# led_dimmer.net
KiCad netlist of a schematic drawn in EAGLE
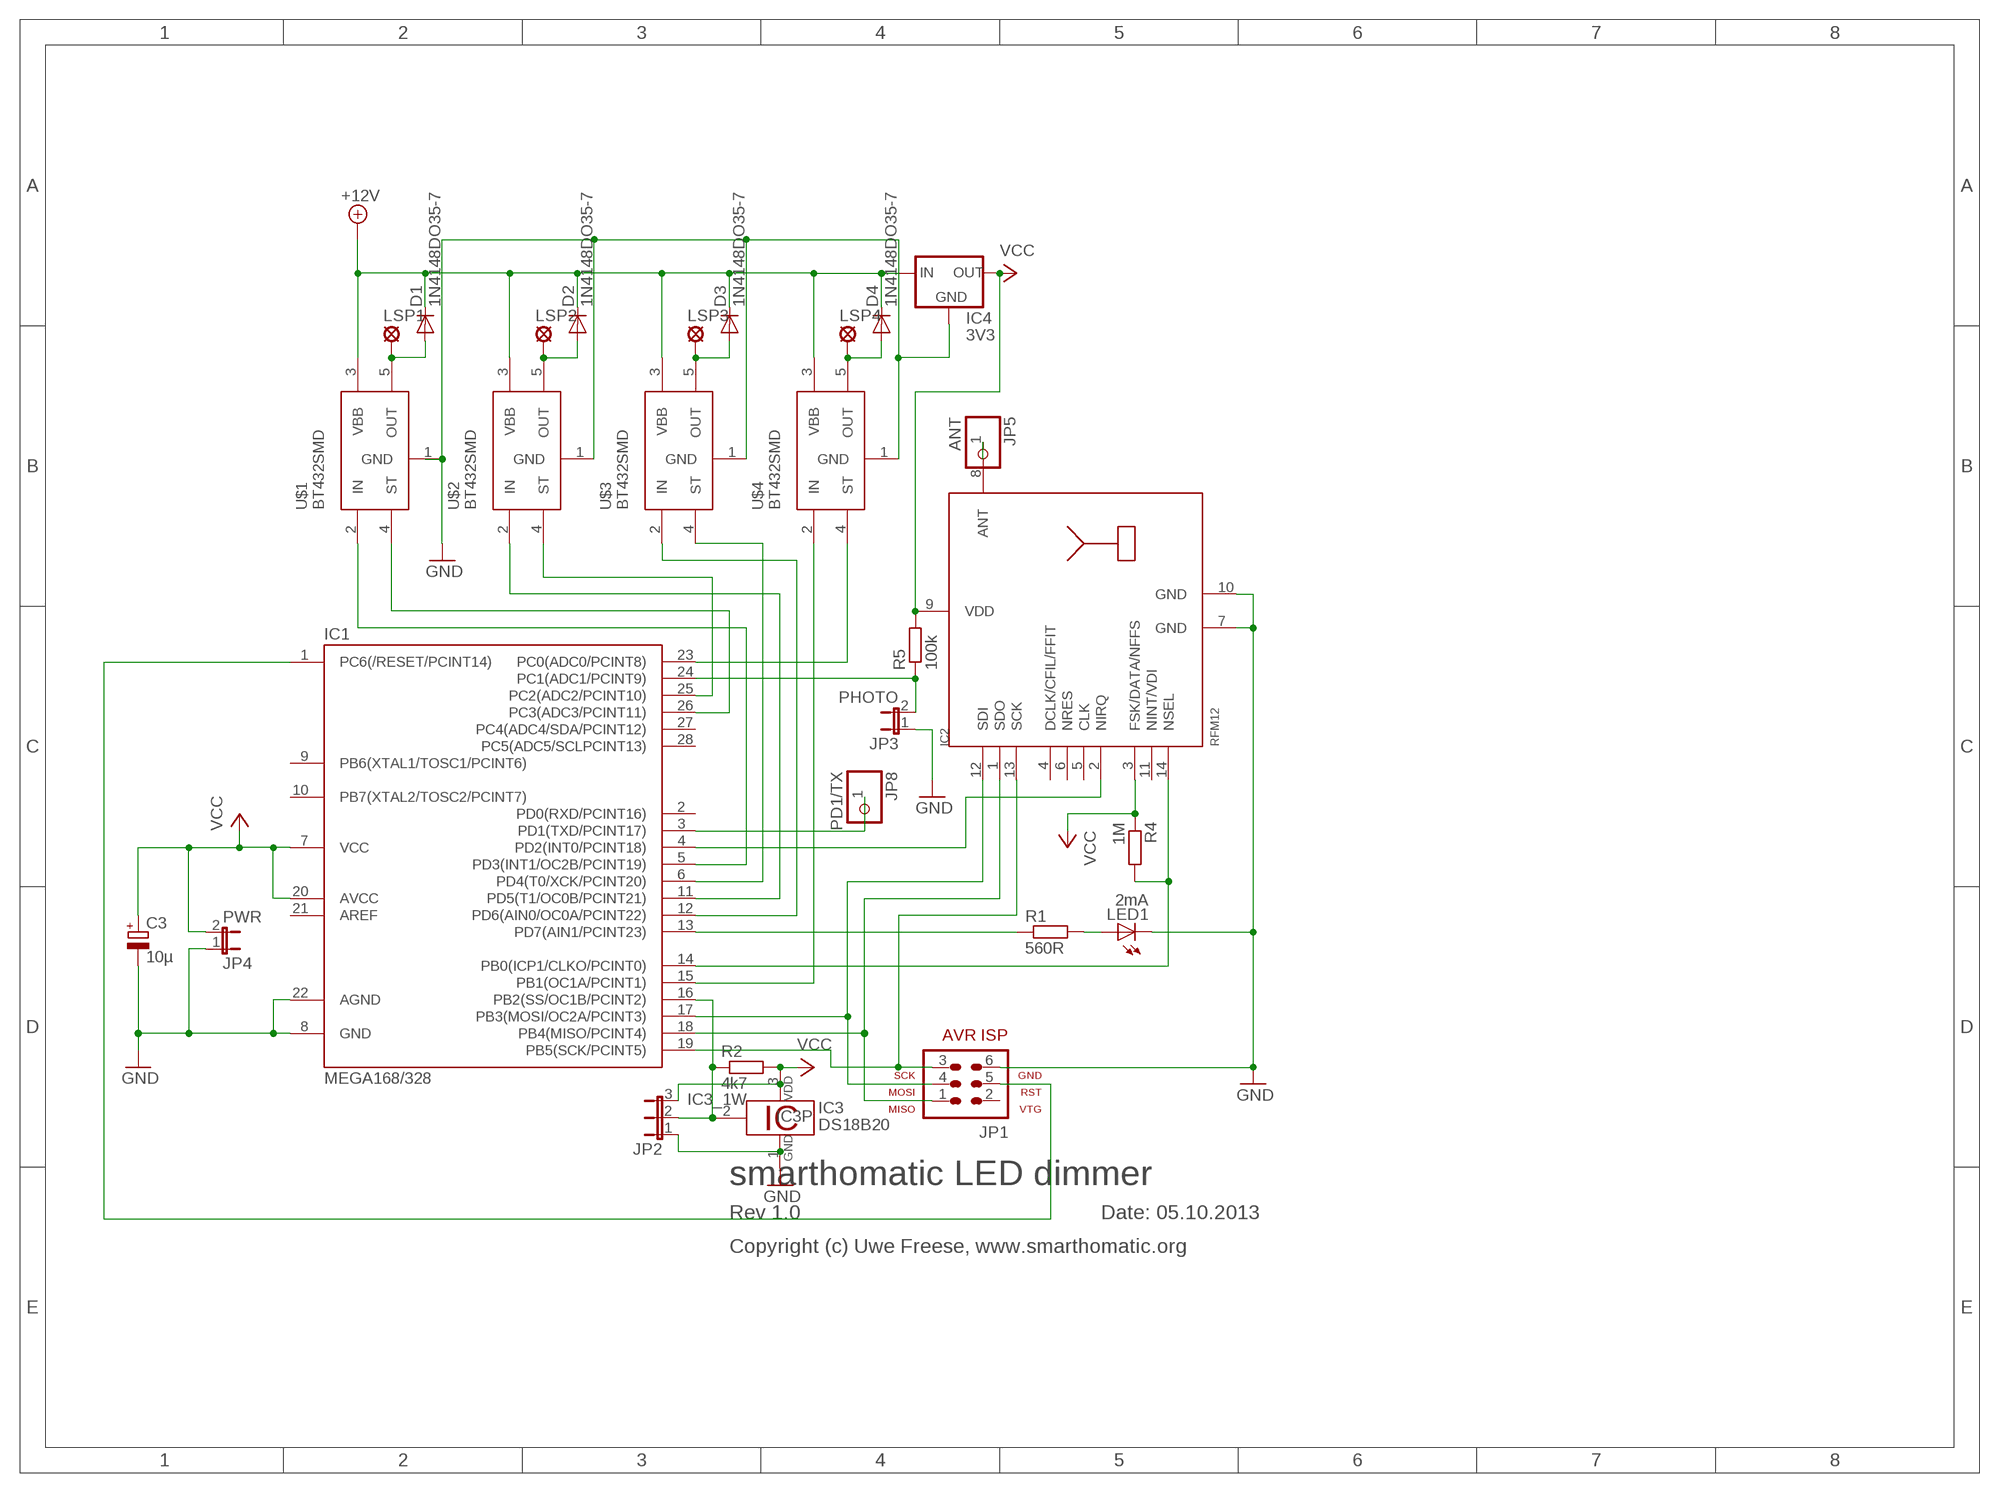
[diagram p0: schematic, sheet 1]

(export (version "E")
  (design (tool "Eeschema 10.0.6"))
  (components
    (comp (ref "C3")
      (value "10µ")
      (footprint "eagle-import:E2,5-6")
      (libsource (lib "eagle-import") (part "CPOL-EUE2.5-6"))
    )
    (comp (ref "D1")
      (value "1N4148DO35-7")
      (footprint "eagle-import:DO35-7")
      (libsource (lib "eagle-import") (part "1N4148DO35-7"))
    )
    (comp (ref "D2")
      (value "1N4148DO35-7")
      (footprint "eagle-import:DO35-7")
      (libsource (lib "eagle-import") (part "1N4148DO35-7"))
    )
    (comp (ref "D3")
      (value "1N4148DO35-7")
      (footprint "eagle-import:DO35-7")
      (libsource (lib "eagle-import") (part "1N4148DO35-7"))
    )
    (comp (ref "D4")
      (value "1N4148DO35-7")
      (footprint "eagle-import:DO35-7")
      (libsource (lib "eagle-import") (part "1N4148DO35-7"))
    )
    (comp (ref "IC1")
      (value "MEGA168/328")
      (footprint "eagle-import:DIL28-3")
      (libsource (lib "eagle-import") (part "MEGA48/88/168-PU"))
    )
    (comp (ref "IC2")
      (value "RFM12")
      (footprint "eagle-import:RFM")
      (libsource (lib "eagle-import") (part "RFM12"))
    )
    (comp (ref "IC3")
      (value "DS18B20")
      (footprint "eagle-import:TO92-")
      (libsource (lib "eagle-import") (part "DS18B20"))
    )
    (comp (ref "IC4")
      (value "3V3")
      (footprint "eagle-import:78LXX")
      (libsource (lib "eagle-import") (part "78LXX"))
    )
    (comp (ref "JP1")
      (value "AVR-ISP-6")
      (footprint "eagle-import:AVR-ISP-6")
      (libsource (lib "eagle-import") (part "AVR-ISP-6"))
    )
    (comp (ref "JP2")
      (value "JP2E")
      (footprint "eagle-import:JP2")
      (libsource (lib "eagle-import") (part "JP2E"))
    )
    (comp (ref "JP3")
      (value "PHOTO")
      (footprint "eagle-import:JP1")
      (libsource (lib "eagle-import") (part "JP1E"))
    )
    (comp (ref "JP4")
      (value "PWR")
      (footprint "eagle-import:JP1")
      (libsource (lib "eagle-import") (part "JP1E"))
    )
    (comp (ref "JP5")
      (value "ANT")
      (footprint "eagle-import:1X01")
      (libsource (lib "eagle-import") (part "PINHD-1X1"))
    )
    (comp (ref "JP8")
      (value "PD1/TX")
      (footprint "eagle-import:1X01")
      (libsource (lib "eagle-import") (part "PINHD-1X1"))
    )
    (comp (ref "LED1")
      (value "2mA")
      (footprint "eagle-import:LED3MM")
      (libsource (lib "eagle-import") (part "LED3MM"))
    )
    (comp (ref "LSP1")
      (value "MCS10B")
      (footprint "eagle-import:MCS10B")
      (libsource (lib "eagle-import") (part "MCS10B"))
    )
    (comp (ref "LSP2")
      (value "MCS10B")
      (footprint "eagle-import:MCS10B")
      (libsource (lib "eagle-import") (part "MCS10B"))
    )
    (comp (ref "LSP3")
      (value "MCS10B")
      (footprint "eagle-import:MCS10B")
      (libsource (lib "eagle-import") (part "MCS10B"))
    )
    (comp (ref "LSP4")
      (value "MCS10B")
      (footprint "eagle-import:MCS10B")
      (libsource (lib "eagle-import") (part "MCS10B"))
    )
    (comp (ref "R1")
      (value "560R")
      (footprint "eagle-import:0207_7")
      (libsource (lib "eagle-import") (part "R-EU_0207/7"))
    )
    (comp (ref "R2")
      (value "4k7")
      (footprint "eagle-import:0207_7")
      (libsource (lib "eagle-import") (part "resistor_R-EU_0207/7"))
    )
    (comp (ref "R4")
      (value "1M")
      (footprint "eagle-import:0207_7")
      (libsource (lib "eagle-import") (part "R-EU_0207/7"))
    )
    (comp (ref "R5")
      (value "100k")
      (footprint "eagle-import:0207_7")
      (libsource (lib "eagle-import") (part "R-EU_0207/7"))
    )
    (comp (ref "U$1")
      (value "BT432SMD")
      (footprint "eagle-import:TO220-58")
      (libsource (lib "eagle-import") (part "BT432SMD"))
    )
    (comp (ref "U$2")
      (value "BT432SMD")
      (footprint "eagle-import:TO220-58")
      (libsource (lib "eagle-import") (part "BT432SMD"))
    )
    (comp (ref "U$3")
      (value "BT432SMD")
      (footprint "eagle-import:TO220-58")
      (libsource (lib "eagle-import") (part "BT432SMD"))
    )
    (comp (ref "U$4")
      (value "BT432SMD")
      (footprint "eagle-import:TO220-58")
      (libsource (lib "eagle-import") (part "BT432SMD"))
    )
  )
  (nets
    (net (code "1") (name "+12V") (class "Default")
      (node (ref "D1") (pin "C") (pinfunction "C_C") (pintype "passive"))
      (node (ref "D2") (pin "C") (pinfunction "C_C") (pintype "passive"))
      (node (ref "D3") (pin "C") (pinfunction "C_C") (pintype "passive"))
      (node (ref "D4") (pin "C") (pinfunction "C_C") (pintype "passive"))
      (node (ref "IC4") (pin "IN") (pinfunction "IN_IN") (pintype "input"))
      (node (ref "U$1") (pin "3") (pinfunction "VBB_3") (pintype "bidirectional"))
      (node (ref "U$2") (pin "3") (pinfunction "VBB_3") (pintype "bidirectional"))
      (node (ref "U$3") (pin "3") (pinfunction "VBB_3") (pintype "bidirectional"))
      (node (ref "U$4") (pin "3") (pinfunction "VBB_3") (pintype "bidirectional"))
    )
    (net (code "2") (name "GND") (class "Default")
      (node (ref "C3") (pin "-") (pinfunction "-_-") (pintype "passive"))
      (node (ref "IC1") (pin "22") (pinfunction "AGND_22") (pintype "power_in"))
      (node (ref "IC1") (pin "8") (pinfunction "GND_8") (pintype "power_in"))
      (node (ref "IC2") (pin "10") (pinfunction "GND_10") (pintype "power_in"))
      (node (ref "IC2") (pin "7") (pinfunction "GND_7") (pintype "power_in"))
      (node (ref "IC3") (pin "1") (pinfunction "GND_1") (pintype "power_in"))
      (node (ref "IC4") (pin "GND") (pinfunction "GND_GND") (pintype "input"))
      (node (ref "JP1") (pin "6") (pinfunction "6_6") (pintype "passive"))
      (node (ref "JP2") (pin "1") (pinfunction "1_1") (pintype "passive"))
      (node (ref "JP3") (pin "1") (pinfunction "1_1") (pintype "passive"))
      (node (ref "JP4") (pin "1") (pinfunction "1_1") (pintype "passive"))
      (node (ref "LED1") (pin "K") (pinfunction "C_K") (pintype "passive"))
      (node (ref "U$1") (pin "1") (pinfunction "GND_1") (pintype "bidirectional"))
      (node (ref "U$2") (pin "1") (pinfunction "GND_1") (pintype "bidirectional"))
      (node (ref "U$3") (pin "1") (pinfunction "GND_1") (pintype "bidirectional"))
      (node (ref "U$4") (pin "1") (pinfunction "GND_1") (pintype "bidirectional"))
    )
    (net (code "3") (name "Net-(IC1-PB0(ICP1{slash}CLKO{slash}PCINT0))") (class "Default")
      (node (ref "IC1") (pin "14") (pinfunction "PB0(ICP1/CLKO/PCINT0)_14") (pintype "bidirectional"))
      (node (ref "IC2") (pin "14") (pinfunction "NSEL_14") (pintype "bidirectional"))
      (node (ref "R4") (pin "2") (pinfunction "2_2") (pintype "passive"))
    )
    (net (code "4") (name "Net-(IC1-PB1(OC1A{slash}PCINT1))") (class "Default")
      (node (ref "IC1") (pin "15") (pinfunction "PB1(OC1A/PCINT1)_15") (pintype "bidirectional"))
      (node (ref "U$4") (pin "2") (pinfunction "IN_2") (pintype "bidirectional"))
    )
    (net (code "5") (name "Net-(IC1-PB2(SS{slash}OC1B{slash}PCINT2))") (class "Default")
      (node (ref "IC1") (pin "16") (pinfunction "PB2(SS/OC1B/PCINT2)_16") (pintype "bidirectional"))
      (node (ref "IC3") (pin "2") (pinfunction "1W_2") (pintype "power_in"))
      (node (ref "JP2") (pin "2") (pinfunction "2_2") (pintype "passive"))
      (node (ref "R2") (pin "1") (pinfunction "1_1") (pintype "passive"))
    )
    (net (code "6") (name "Net-(IC1-PB3(MOSI{slash}OC2A{slash}PCINT3))") (class "Default")
      (node (ref "IC1") (pin "17") (pinfunction "PB3(MOSI/OC2A/PCINT3)_17") (pintype "bidirectional"))
      (node (ref "IC2") (pin "12") (pinfunction "SDI_12") (pintype "bidirectional"))
      (node (ref "JP1") (pin "4") (pinfunction "4_4") (pintype "passive"))
    )
    (net (code "7") (name "Net-(IC1-PB4(MISO{slash}PCINT4))") (class "Default")
      (node (ref "IC1") (pin "18") (pinfunction "PB4(MISO/PCINT4)_18") (pintype "bidirectional"))
      (node (ref "IC2") (pin "1") (pinfunction "SDO_1") (pintype "bidirectional"))
      (node (ref "JP1") (pin "1") (pinfunction "1_1") (pintype "passive"))
    )
    (net (code "8") (name "Net-(IC1-PB5(SCK{slash}PCINT5))") (class "Default")
      (node (ref "IC1") (pin "19") (pinfunction "PB5(SCK/PCINT5)_19") (pintype "bidirectional"))
      (node (ref "IC2") (pin "13") (pinfunction "SCK_13") (pintype "bidirectional"))
      (node (ref "JP1") (pin "3") (pinfunction "3_3") (pintype "passive"))
    )
    (net (code "9") (name "Net-(IC1-PC0(ADC0{slash}PCINT8))") (class "Default")
      (node (ref "IC1") (pin "23") (pinfunction "PC0(ADC0/PCINT8)_23") (pintype "bidirectional"))
      (node (ref "U$4") (pin "4") (pinfunction "ST_4") (pintype "bidirectional"))
    )
    (net (code "10") (name "Net-(IC1-PC1(ADC1{slash}PCINT9))") (class "Default")
      (node (ref "IC1") (pin "24") (pinfunction "PC1(ADC1/PCINT9)_24") (pintype "bidirectional"))
      (node (ref "JP3") (pin "2") (pinfunction "2_2") (pintype "passive"))
      (node (ref "R5") (pin "1") (pinfunction "1_1") (pintype "passive"))
    )
    (net (code "11") (name "Net-(IC1-PC2(ADC2{slash}PCINT10))") (class "Default")
      (node (ref "IC1") (pin "25") (pinfunction "PC2(ADC2/PCINT10)_25") (pintype "bidirectional"))
      (node (ref "U$2") (pin "4") (pinfunction "ST_4") (pintype "bidirectional"))
    )
    (net (code "12") (name "Net-(IC1-PC3(ADC3{slash}PCINT11))") (class "Default")
      (node (ref "IC1") (pin "26") (pinfunction "PC3(ADC3/PCINT11)_26") (pintype "bidirectional"))
      (node (ref "U$1") (pin "4") (pinfunction "ST_4") (pintype "bidirectional"))
    )
    (net (code "13") (name "Net-(IC1-PC6({slash}RESET{slash}PCINT14))") (class "Default")
      (node (ref "IC1") (pin "1") (pinfunction "PC6(/RESET/PCINT14)_1") (pintype "bidirectional"))
      (node (ref "JP1") (pin "5") (pinfunction "5_5") (pintype "passive"))
    )
    (net (code "14") (name "Net-(IC1-PD1(TXD{slash}PCINT17))") (class "Default")
      (node (ref "IC1") (pin "3") (pinfunction "PD1(TXD/PCINT17)_3") (pintype "bidirectional"))
      (node (ref "JP8") (pin "1") (pinfunction "1_1") (pintype "passive"))
    )
    (net (code "15") (name "Net-(IC1-PD2(INT0{slash}PCINT18))") (class "Default")
      (node (ref "IC1") (pin "4") (pinfunction "PD2(INT0/PCINT18)_4") (pintype "bidirectional"))
      (node (ref "IC2") (pin "2") (pinfunction "NIRQ_2") (pintype "bidirectional"))
    )
    (net (code "16") (name "Net-(IC1-PD3(INT1{slash}OC2B{slash}PCINT19))") (class "Default")
      (node (ref "IC1") (pin "5") (pinfunction "PD3(INT1/OC2B/PCINT19)_5") (pintype "bidirectional"))
      (node (ref "U$1") (pin "2") (pinfunction "IN_2") (pintype "bidirectional"))
    )
    (net (code "17") (name "Net-(IC1-PD4(T0{slash}XCK{slash}PCINT20))") (class "Default")
      (node (ref "IC1") (pin "6") (pinfunction "PD4(T0/XCK/PCINT20)_6") (pintype "bidirectional"))
      (node (ref "U$3") (pin "4") (pinfunction "ST_4") (pintype "bidirectional"))
    )
    (net (code "18") (name "Net-(IC1-PD5(T1{slash}OC0B{slash}PCINT21))") (class "Default")
      (node (ref "IC1") (pin "11") (pinfunction "PD5(T1/OC0B/PCINT21)_11") (pintype "bidirectional"))
      (node (ref "U$2") (pin "2") (pinfunction "IN_2") (pintype "bidirectional"))
    )
    (net (code "19") (name "Net-(IC1-PD6(AIN0{slash}OC0A{slash}PCINT22))") (class "Default")
      (node (ref "IC1") (pin "12") (pinfunction "PD6(AIN0/OC0A/PCINT22)_12") (pintype "bidirectional"))
      (node (ref "U$3") (pin "2") (pinfunction "IN_2") (pintype "bidirectional"))
    )
    (net (code "20") (name "Net-(IC1-PD7(AIN1{slash}PCINT23))") (class "Default")
      (node (ref "IC1") (pin "13") (pinfunction "PD7(AIN1/PCINT23)_13") (pintype "bidirectional"))
      (node (ref "R1") (pin "1") (pinfunction "1_1") (pintype "passive"))
    )
    (net (code "21") (name "Net-(IC2-ANT)") (class "Default")
      (node (ref "IC2") (pin "8") (pinfunction "ANT_8") (pintype "output"))
      (node (ref "JP5") (pin "1") (pinfunction "1_1") (pintype "passive"))
    )
    (net (code "22") (name "Net-(LED1-PadA)") (class "Default")
      (node (ref "LED1") (pin "A") (pinfunction "A_A") (pintype "passive"))
      (node (ref "R1") (pin "2") (pinfunction "2_2") (pintype "passive"))
    )
    (net (code "23") (name "Net-(U$1-OUT)") (class "Default")
      (node (ref "D1") (pin "A") (pinfunction "A_A") (pintype "passive"))
      (node (ref "LSP1") (pin "MP") (pinfunction "MP_MP") (pintype "passive"))
      (node (ref "U$1") (pin "5") (pinfunction "OUT_5") (pintype "bidirectional"))
    )
    (net (code "24") (name "Net-(U$2-OUT)") (class "Default")
      (node (ref "D2") (pin "A") (pinfunction "A_A") (pintype "passive"))
      (node (ref "LSP2") (pin "MP") (pinfunction "MP_MP") (pintype "passive"))
      (node (ref "U$2") (pin "5") (pinfunction "OUT_5") (pintype "bidirectional"))
    )
    (net (code "25") (name "Net-(U$3-OUT)") (class "Default")
      (node (ref "D3") (pin "A") (pinfunction "A_A") (pintype "passive"))
      (node (ref "LSP3") (pin "MP") (pinfunction "MP_MP") (pintype "passive"))
      (node (ref "U$3") (pin "5") (pinfunction "OUT_5") (pintype "bidirectional"))
    )
    (net (code "26") (name "Net-(U$4-OUT)") (class "Default")
      (node (ref "D4") (pin "A") (pinfunction "A_A") (pintype "passive"))
      (node (ref "LSP4") (pin "MP") (pinfunction "MP_MP") (pintype "passive"))
      (node (ref "U$4") (pin "5") (pinfunction "OUT_5") (pintype "bidirectional"))
    )
    (net (code "27") (name "VCC") (class "Default")
      (node (ref "C3") (pin "+") (pinfunction "+_+") (pintype "passive"))
      (node (ref "IC1") (pin "20") (pinfunction "AVCC_20") (pintype "passive"))
      (node (ref "IC1") (pin "7") (pinfunction "VCC_7") (pintype "power_in"))
      (node (ref "IC2") (pin "3") (pinfunction "FSK/DATA/NFFS_3") (pintype "bidirectional"))
      (node (ref "IC2") (pin "9") (pinfunction "VDD_9") (pintype "power_in"))
      (node (ref "IC3") (pin "3") (pinfunction "VDD_3") (pintype "power_in"))
      (node (ref "IC4") (pin "OUT") (pinfunction "OUT_OUT") (pintype "passive"))
      (node (ref "JP2") (pin "3") (pinfunction "3_3") (pintype "passive"))
      (node (ref "JP4") (pin "2") (pinfunction "2_2") (pintype "passive"))
      (node (ref "R2") (pin "2") (pinfunction "2_2") (pintype "passive"))
      (node (ref "R4") (pin "1") (pinfunction "1_1") (pintype "passive"))
      (node (ref "R5") (pin "2") (pinfunction "2_2") (pintype "passive"))
    )
    (net (code "28") (name "unconnected-(IC1-AREF-Pad21)") (class "Default")
      (node (ref "IC1") (pin "21") (pinfunction "AREF_21") (pintype "passive"))
    )
    (net (code "29") (name "unconnected-(IC1-PB6(XTAL1{slash}TOSC1{slash}PCINT6)-Pad9)") (class "Default")
      (node (ref "IC1") (pin "9") (pinfunction "PB6(XTAL1/TOSC1/PCINT6)_9") (pintype "bidirectional"))
    )
    (net (code "30") (name "unconnected-(IC1-PB7(XTAL2{slash}TOSC2{slash}PCINT7)-Pad10)") (class "Default")
      (node (ref "IC1") (pin "10") (pinfunction "PB7(XTAL2/TOSC2/PCINT7)_10") (pintype "bidirectional"))
    )
    (net (code "31") (name "unconnected-(IC1-PC4(ADC4{slash}SDA{slash}PCINT12)-Pad27)") (class "Default")
      (node (ref "IC1") (pin "27") (pinfunction "PC4(ADC4/SDA/PCINT12)_27") (pintype "bidirectional"))
    )
    (net (code "32") (name "unconnected-(IC1-PC5(ADC5{slash}SCLPCINT13)-Pad28)") (class "Default")
      (node (ref "IC1") (pin "28") (pinfunction "PC5(ADC5/SCLPCINT13)_28") (pintype "bidirectional"))
    )
    (net (code "33") (name "unconnected-(IC1-PD0(RXD{slash}PCINT16)-Pad2)") (class "Default")
      (node (ref "IC1") (pin "2") (pinfunction "PD0(RXD/PCINT16)_2") (pintype "bidirectional"))
    )
    (net (code "34") (name "unconnected-(IC2-CLK-Pad5)") (class "Default")
      (node (ref "IC2") (pin "5") (pinfunction "CLK_5") (pintype "bidirectional"))
    )
    (net (code "35") (name "unconnected-(IC2-DCLK{slash}CFIL{slash}FFIT-Pad4)") (class "Default")
      (node (ref "IC2") (pin "4") (pinfunction "DCLK/CFIL/FFIT_4") (pintype "bidirectional"))
    )
    (net (code "36") (name "unconnected-(IC2-NINT{slash}VDI-Pad11)") (class "Default")
      (node (ref "IC2") (pin "11") (pinfunction "NINT/VDI_11") (pintype "bidirectional"))
    )
    (net (code "37") (name "unconnected-(IC2-NRES-Pad6)") (class "Default")
      (node (ref "IC2") (pin "6") (pinfunction "NRES_6") (pintype "bidirectional"))
    )
    (net (code "38") (name "unconnected-(JP1-Pad2)") (class "Default")
      (node (ref "JP1") (pin "2") (pinfunction "2_2") (pintype "passive"))
    )
  )
)
